# SDVX_Mini.net
KiCad netlist of a schematic drawn in Altium Designer
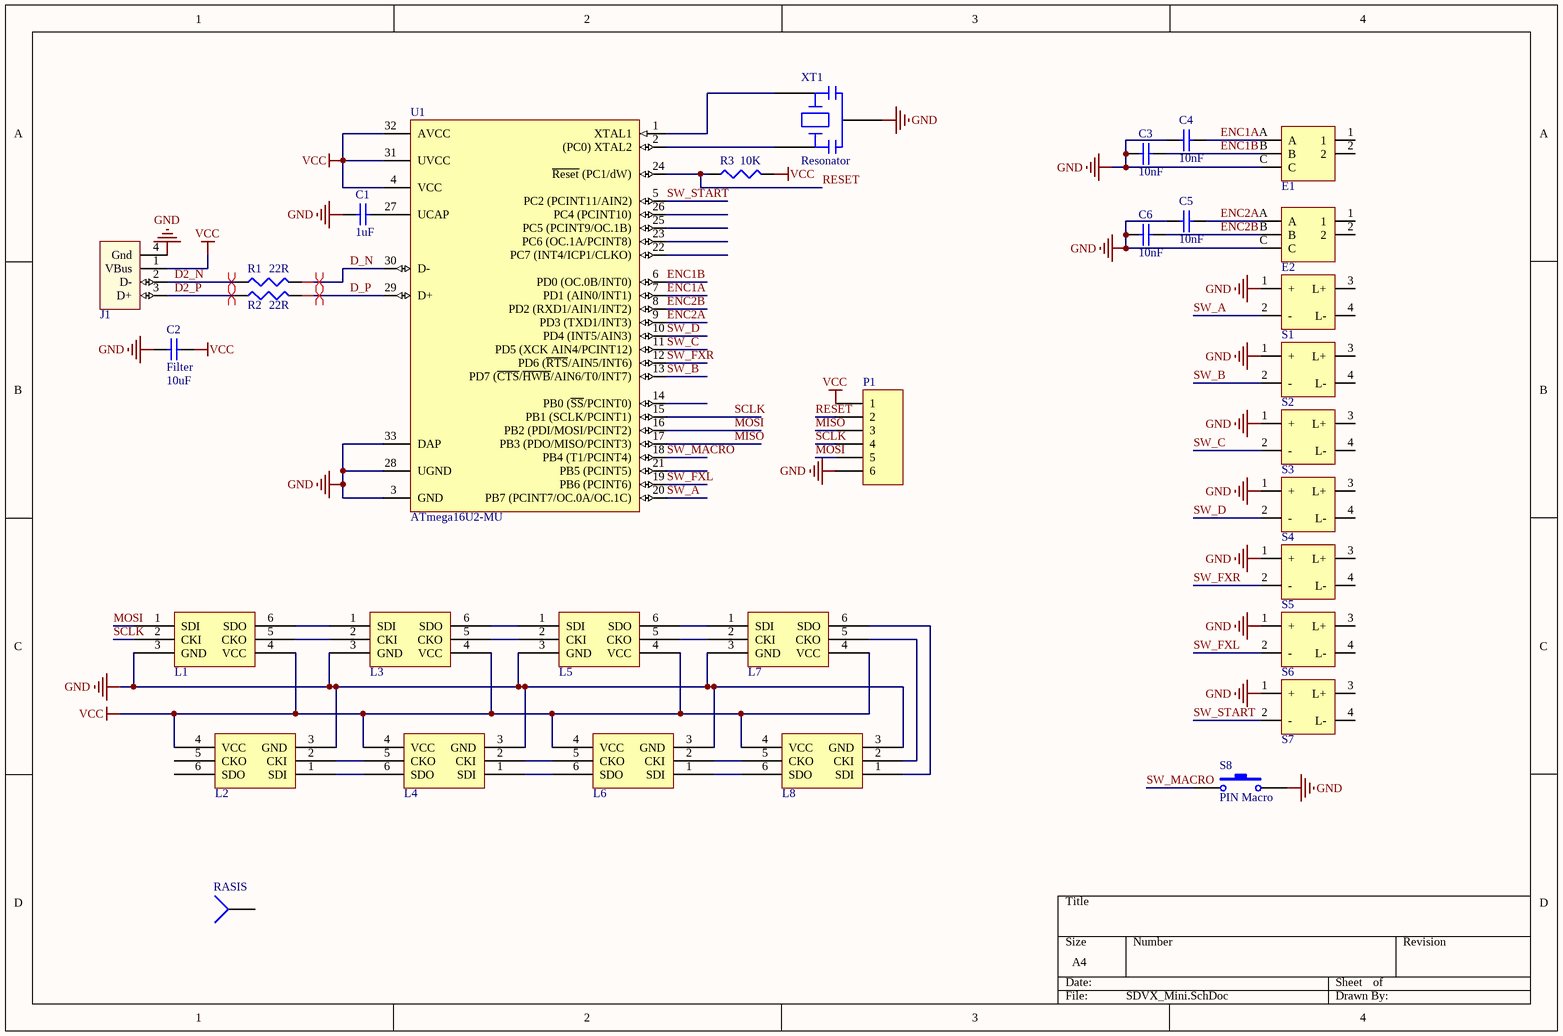
[diagram p0: SDVX_Mini.SchDoc]

(export (version "E")
  (design (tool "Eeschema 10.0.6"))
  (components
    (comp (ref "C1")
      (value "1uF")
      (footprint "1608[0603]")
      (description "Capacitor (Semiconductor SIM Model)")
      (fields (field (name "Comment") "Cap Semi") (field (name "PUBLISHER") "Altium Limited"))
      (libsource (lib "Miscellaneous Devices") (part "Cap Semi"))
    )
    (comp (ref "C2")
      (value "Filter")
      (footprint "1608[0603]")
      (description "Capacitor (Semiconductor SIM Model)")
      (fields (field (name "ALTIUM_VALUE") "10uF") (field (name "PUBLISHER") "Altium Limited"))
      (libsource (lib "Miscellaneous Devices") (part "Cap Semi"))
    )
    (comp (ref "C3")
      (value "10nF")
      (footprint "1608[0603]")
      (description "Capacitor (Semiconductor SIM Model)")
      (fields (field (name "Comment") "Cap Semi") (field (name "PUBLISHER") "Altium Limited"))
      (libsource (lib "Miscellaneous Devices") (part "Cap Semi"))
    )
    (comp (ref "C4")
      (value "10nF")
      (footprint "1608[0603]")
      (description "Capacitor (Semiconductor SIM Model)")
      (fields (field (name "Comment") "Cap Semi") (field (name "PUBLISHER") "Altium Limited"))
      (libsource (lib "Miscellaneous Devices") (part "Cap Semi"))
    )
    (comp (ref "C5")
      (value "10nF")
      (footprint "1608[0603]")
      (description "Capacitor (Semiconductor SIM Model)")
      (fields (field (name "Comment") "Cap Semi") (field (name "PUBLISHER") "Altium Limited"))
      (libsource (lib "Miscellaneous Devices") (part "Cap Semi"))
    )
    (comp (ref "C6")
      (value "10nF")
      (footprint "1608[0603]")
      (description "Capacitor (Semiconductor SIM Model)")
      (fields (field (name "Comment") "Cap Semi") (field (name "PUBLISHER") "Altium Limited"))
      (libsource (lib "Miscellaneous Devices") (part "Cap Semi"))
    )
    (comp (ref "E1")
      (value "ENCODER_SWITCH")
      (footprint "ENCODER_NOSWITCH_BOURNS_PEC16-4")
      (libsource (lib "MonParts") (part "ENCODER_SWITCH"))
    )
    (comp (ref "E2")
      (value "ENCODER_SWITCH")
      (footprint "ENCODER_NOSWITCH_BOURNS_PEC16-4")
      (libsource (lib "MonParts") (part "ENCODER_SWITCH"))
    )
    (comp (ref "J1")
      (value "USB Connector")
      (footprint "MICRO-USB-SEEED")
      (libsource (lib "MonParts") (part "USB Connector"))
    )
    (comp (ref "L1") (value "SK9822") (footprint "SK9822") (libsource (lib "") (part "SK9822_1")))
    (comp (ref "L2") (value "SK9822") (footprint "SK9822") (libsource (lib "MonParts") (part "SK9822")))
    (comp (ref "L3") (value "SK9822") (footprint "SK9822") (libsource (lib "") (part "SK9822_1")))
    (comp (ref "L4") (value "SK9822") (footprint "SK9822") (libsource (lib "MonParts") (part "SK9822")))
    (comp (ref "L5") (value "SK9822") (footprint "SK9822") (libsource (lib "") (part "SK9822_1")))
    (comp (ref "L6") (value "SK9822") (footprint "SK9822") (libsource (lib "MonParts") (part "SK9822")))
    (comp (ref "L7") (value "SK9822") (footprint "SK9822") (libsource (lib "") (part "SK9822_1")))
    (comp (ref "L8") (value "SK9822") (footprint "SK9822") (libsource (lib "MonParts") (part "SK9822")))
    (comp (ref "P1")
      (value "Header 6")
      (footprint "HDR1X6")
      (description "Header, 6-Pin")
      (fields (field (name "PUBLISHER") "Altium Limited"))
      (libsource (lib "Miscellaneous Connectors") (part "Header 6"))
    )
    (comp (ref "R1")
      (value "22R")
      (footprint "J1-0603")
      (description "Resistor")
      (fields (field (name "PUBLISHER") "Altium Limited"))
      (libsource (lib "Miscellaneous Devices") (part "Res3"))
    )
    (comp (ref "R2")
      (value "22R")
      (footprint "J1-0603")
      (description "Resistor")
      (fields (field (name "Comment") "Res3") (field (name "PUBLISHER") "Altium Limited"))
      (libsource (lib "Miscellaneous Devices") (part "Res3"))
    )
    (comp (ref "R3")
      (value "10K")
      (footprint "J1-0603")
      (description "Resistor")
      (fields (field (name "PUBLISHER") "Altium Limited"))
      (libsource (lib "Miscellaneous Devices") (part "Res3"))
    )
    (comp (ref "RASIS")
      (value "Imp")
      (footprint "RASIS_INVERT")
      (description "Socket")
      (fields (field (name "PUBLISHER") "Altium Limited"))
      (libsource (lib "Miscellaneous Connectors") (part "Socket"))
    )
    (comp (ref "S1")
      (value "Cherry MX")
      (footprint "CHERRYMX_NO_LED")
      (libsource (lib "MonParts") (part "Cherry MX"))
    )
    (comp (ref "S2")
      (value "Cherry MX")
      (footprint "CHERRYMX_NO_LED")
      (libsource (lib "MonParts") (part "Cherry MX"))
    )
    (comp (ref "S3")
      (value "Cherry MX")
      (footprint "CHERRYMX_NO_LED")
      (libsource (lib "MonParts") (part "Cherry MX"))
    )
    (comp (ref "S4")
      (value "Cherry MX")
      (footprint "CHERRYMX_NO_LED")
      (libsource (lib "MonParts") (part "Cherry MX"))
    )
    (comp (ref "S5")
      (value "Cherry MX")
      (footprint "CHERRYMX_NO_LED")
      (libsource (lib "MonParts") (part "Cherry MX"))
    )
    (comp (ref "S6")
      (value "Cherry MX")
      (footprint "CHERRYMX_NO_LED")
      (libsource (lib "MonParts") (part "Cherry MX"))
    )
    (comp (ref "S7")
      (value "Cherry MX")
      (footprint "CHERRYMX_NO_LED")
      (libsource (lib "MonParts") (part "Cherry MX"))
    )
    (comp (ref "S8")
      (value "PIN Macro")
      (footprint "SWITCH_KSC421J")
      (description "Switch")
      (fields (field (name "PUBLISHER") "Altium Limited"))
      (libsource (lib "Miscellaneous Devices") (part "SW-PB"))
    )
    (comp (ref "U1")
      (value "ATmega16U2-MU")
      (footprint "ATMEGA16U2-NOTHERMAL")
      (libsource (lib "Atmel Microcontroller megaAVR") (part "ATmega16U2-MU"))
    )
    (comp (ref "XT1")
      (value "Resonator")
      (footprint "RESONATOR_CSTCE_V")
      (libsource (lib "MonParts") (part "Resonator"))
    )
  )
  (nets
    (net (code "1") (name "/D2_N") (class "Default")
      (node (ref "J1") (pin "2") (pinfunction "D-_2") (pintype "bidirectional"))
      (node (ref "R1") (pin "1") (pinfunction "1_1") (pintype "passive"))
    )
    (net (code "2") (name "/D2_P") (class "Default")
      (node (ref "J1") (pin "3") (pinfunction "D+_3") (pintype "bidirectional"))
      (node (ref "R2") (pin "1") (pinfunction "1_1") (pintype "passive"))
    )
    (net (code "3") (name "/D_N") (class "Default")
      (node (ref "R1") (pin "2") (pinfunction "2_2") (pintype "passive"))
      (node (ref "U1") (pin "30") (pinfunction "D-_30") (pintype "bidirectional"))
    )
    (net (code "4") (name "/D_P") (class "Default")
      (node (ref "R2") (pin "2") (pinfunction "2_2") (pintype "passive"))
      (node (ref "U1") (pin "29") (pinfunction "D+_29") (pintype "bidirectional"))
    )
    (net (code "5") (name "/ENC1A") (class "Default")
      (node (ref "C4") (pin "1") (pinfunction "1_1") (pintype "passive"))
      (node (ref "E1") (pin "A") (pinfunction "A_A") (pintype "passive"))
      (node (ref "U1") (pin "7") (pinfunction "PD1_(AIN0/INT1)_7") (pintype "bidirectional"))
    )
    (net (code "6") (name "/ENC1B") (class "Default")
      (node (ref "C3") (pin "2") (pinfunction "2_2") (pintype "passive"))
      (node (ref "E1") (pin "B") (pinfunction "B_B") (pintype "passive"))
      (node (ref "U1") (pin "6") (pinfunction "PD0_(OC.0B/INT0)_6") (pintype "bidirectional"))
    )
    (net (code "7") (name "/ENC2A") (class "Default")
      (node (ref "C5") (pin "1") (pinfunction "1_1") (pintype "passive"))
      (node (ref "E2") (pin "A") (pinfunction "A_A") (pintype "passive"))
      (node (ref "U1") (pin "9") (pinfunction "PD3_(TXD1/INT3)_9") (pintype "bidirectional"))
    )
    (net (code "8") (name "/ENC2B") (class "Default")
      (node (ref "C6") (pin "2") (pinfunction "2_2") (pintype "passive"))
      (node (ref "E2") (pin "B") (pinfunction "B_B") (pintype "passive"))
      (node (ref "U1") (pin "8") (pinfunction "PD2_(RXD1/AIN1/INT2)_8") (pintype "bidirectional"))
    )
    (net (code "9") (name "/MISO") (class "Default")
      (node (ref "P1") (pin "3") (pinfunction "3_3") (pintype "passive"))
      (node (ref "U1") (pin "17") (pinfunction "PB3_(PDO/MISO/PCINT3)_17") (pintype "bidirectional"))
    )
    (net (code "10") (name "/MOSI") (class "Default")
      (node (ref "L1") (pin "1") (pinfunction "SDI_1") (pintype "passive"))
      (node (ref "P1") (pin "5") (pinfunction "5_5") (pintype "passive"))
      (node (ref "U1") (pin "16") (pinfunction "PB2_(PDI/MOSI/PCINT2)_16") (pintype "bidirectional"))
    )
    (net (code "11") (name "/RESET") (class "Default")
      (node (ref "P1") (pin "2") (pinfunction "2_2") (pintype "passive"))
      (node (ref "R3") (pin "1") (pinfunction "1_1") (pintype "passive"))
      (node (ref "U1") (pin "24") (pinfunction "~{Reset}_(PC1/dW)_24") (pintype "bidirectional"))
    )
    (net (code "12") (name "/SCLK") (class "Default")
      (node (ref "L1") (pin "2") (pinfunction "CKI_2") (pintype "passive"))
      (node (ref "P1") (pin "4") (pinfunction "4_4") (pintype "passive"))
      (node (ref "U1") (pin "15") (pinfunction "PB1_(SCLK/PCINT1)_15") (pintype "bidirectional"))
    )
    (net (code "13") (name "/SW_A") (class "Default")
      (node (ref "S1") (pin "2") (pinfunction "-_2") (pintype "passive"))
      (node (ref "U1") (pin "20") (pinfunction "PB7_(PCINT7/OC.0A/OC.1C)_20") (pintype "bidirectional"))
    )
    (net (code "14") (name "/SW_B") (class "Default")
      (node (ref "S2") (pin "2") (pinfunction "-_2") (pintype "passive"))
      (node (ref "U1") (pin "13") (pinfunction "PD7_(~{CTS}/~{HWB}/AIN6/T0/INT7)_13") (pintype "bidirectional"))
    )
    (net (code "15") (name "/SW_C") (class "Default")
      (node (ref "S3") (pin "2") (pinfunction "-_2") (pintype "passive"))
      (node (ref "U1") (pin "11") (pinfunction "PD5_(XCK_AIN4/PCINT12)_11") (pintype "bidirectional"))
    )
    (net (code "16") (name "/SW_D") (class "Default")
      (node (ref "S4") (pin "2") (pinfunction "-_2") (pintype "passive"))
      (node (ref "U1") (pin "10") (pinfunction "PD4_(INT5/AIN3)_10") (pintype "bidirectional"))
    )
    (net (code "17") (name "/SW_FXL") (class "Default")
      (node (ref "S6") (pin "2") (pinfunction "-_2") (pintype "passive"))
      (node (ref "U1") (pin "19") (pinfunction "PB6_(PCINT6)_19") (pintype "bidirectional"))
    )
    (net (code "18") (name "/SW_FXR") (class "Default")
      (node (ref "S5") (pin "2") (pinfunction "-_2") (pintype "passive"))
      (node (ref "U1") (pin "12") (pinfunction "PD6_(~{RTS}/AIN5/INT6)_12") (pintype "bidirectional"))
    )
    (net (code "19") (name "/SW_MACRO") (class "Default")
      (node (ref "S8") (pin "1") (pinfunction "1_1") (pintype "passive"))
      (node (ref "U1") (pin "18") (pinfunction "PB4_(T1/PCINT4)_18") (pintype "bidirectional"))
    )
    (net (code "20") (name "/SW_START") (class "Default")
      (node (ref "S7") (pin "2") (pinfunction "-_2") (pintype "passive"))
      (node (ref "U1") (pin "5") (pinfunction "PC2_(PCINT11/AIN2)_5") (pintype "bidirectional"))
    )
    (net (code "21") (name "GND") (class "Default")
      (node (ref "C1") (pin "2") (pinfunction "2_2") (pintype "passive"))
      (node (ref "C2") (pin "2") (pinfunction "2_2") (pintype "passive"))
      (node (ref "C3") (pin "1") (pinfunction "1_1") (pintype "passive"))
      (node (ref "C4") (pin "2") (pinfunction "2_2") (pintype "passive"))
      (node (ref "C5") (pin "2") (pinfunction "2_2") (pintype "passive"))
      (node (ref "C6") (pin "1") (pinfunction "1_1") (pintype "passive"))
      (node (ref "E1") (pin "C") (pinfunction "C_C") (pintype "passive"))
      (node (ref "E2") (pin "C") (pinfunction "C_C") (pintype "passive"))
      (node (ref "J1") (pin "4") (pinfunction "Gnd_4") (pintype "power_in"))
      (node (ref "L1") (pin "3") (pinfunction "GND_3") (pintype "passive"))
      (node (ref "L2") (pin "3") (pinfunction "GND_3") (pintype "passive"))
      (node (ref "L3") (pin "3") (pinfunction "GND_3") (pintype "passive"))
      (node (ref "L4") (pin "3") (pinfunction "GND_3") (pintype "passive"))
      (node (ref "L5") (pin "3") (pinfunction "GND_3") (pintype "passive"))
      (node (ref "L6") (pin "3") (pinfunction "GND_3") (pintype "passive"))
      (node (ref "L7") (pin "3") (pinfunction "GND_3") (pintype "passive"))
      (node (ref "L8") (pin "3") (pinfunction "GND_3") (pintype "passive"))
      (node (ref "P1") (pin "6") (pinfunction "6_6") (pintype "passive"))
      (node (ref "S1") (pin "1") (pinfunction "+_1") (pintype "passive"))
      (node (ref "S2") (pin "1") (pinfunction "+_1") (pintype "passive"))
      (node (ref "S3") (pin "1") (pinfunction "+_1") (pintype "passive"))
      (node (ref "S4") (pin "1") (pinfunction "+_1") (pintype "passive"))
      (node (ref "S5") (pin "1") (pinfunction "+_1") (pintype "passive"))
      (node (ref "S6") (pin "1") (pinfunction "+_1") (pintype "passive"))
      (node (ref "S7") (pin "1") (pinfunction "+_1") (pintype "passive"))
      (node (ref "S8") (pin "2") (pinfunction "2_2") (pintype "passive"))
      (node (ref "U1") (pin "28") (pinfunction "UGND_28") (pintype "power_in"))
      (node (ref "U1") (pin "3") (pinfunction "GND_3") (pintype "power_in"))
      (node (ref "U1") (pin "33") (pinfunction "DAP_33") (pintype "power_in"))
      (node (ref "XT1") (pin "2") (pinfunction "2_2") (pintype "passive"))
    )
    (net (code "22") (name "Net-(L1-CKO)") (class "Default")
      (node (ref "L1") (pin "5") (pinfunction "CKO_5") (pintype "passive"))
      (node (ref "L3") (pin "2") (pinfunction "CKI_2") (pintype "passive"))
    )
    (net (code "23") (name "Net-(L1-SDO)") (class "Default")
      (node (ref "L1") (pin "6") (pinfunction "SDO_6") (pintype "passive"))
      (node (ref "L3") (pin "1") (pinfunction "SDI_1") (pintype "passive"))
    )
    (net (code "24") (name "Net-(L2-CKI)") (class "Default")
      (node (ref "L2") (pin "2") (pinfunction "CKI_2") (pintype "passive"))
      (node (ref "L4") (pin "5") (pinfunction "CKO_5") (pintype "passive"))
    )
    (net (code "25") (name "Net-(L2-SDI)") (class "Default")
      (node (ref "L2") (pin "1") (pinfunction "SDI_1") (pintype "passive"))
      (node (ref "L4") (pin "6") (pinfunction "SDO_6") (pintype "passive"))
    )
    (net (code "26") (name "Net-(L3-CKO)") (class "Default")
      (node (ref "L3") (pin "5") (pinfunction "CKO_5") (pintype "passive"))
      (node (ref "L5") (pin "2") (pinfunction "CKI_2") (pintype "passive"))
    )
    (net (code "27") (name "Net-(L3-SDO)") (class "Default")
      (node (ref "L3") (pin "6") (pinfunction "SDO_6") (pintype "passive"))
      (node (ref "L5") (pin "1") (pinfunction "SDI_1") (pintype "passive"))
    )
    (net (code "28") (name "Net-(L4-CKI)") (class "Default")
      (node (ref "L4") (pin "2") (pinfunction "CKI_2") (pintype "passive"))
      (node (ref "L6") (pin "5") (pinfunction "CKO_5") (pintype "passive"))
    )
    (net (code "29") (name "Net-(L4-SDI)") (class "Default")
      (node (ref "L4") (pin "1") (pinfunction "SDI_1") (pintype "passive"))
      (node (ref "L6") (pin "6") (pinfunction "SDO_6") (pintype "passive"))
    )
    (net (code "30") (name "Net-(L5-CKO)") (class "Default")
      (node (ref "L5") (pin "5") (pinfunction "CKO_5") (pintype "passive"))
      (node (ref "L7") (pin "2") (pinfunction "CKI_2") (pintype "passive"))
    )
    (net (code "31") (name "Net-(L5-SDO)") (class "Default")
      (node (ref "L5") (pin "6") (pinfunction "SDO_6") (pintype "passive"))
      (node (ref "L7") (pin "1") (pinfunction "SDI_1") (pintype "passive"))
    )
    (net (code "32") (name "Net-(L6-CKI)") (class "Default")
      (node (ref "L6") (pin "2") (pinfunction "CKI_2") (pintype "passive"))
      (node (ref "L8") (pin "5") (pinfunction "CKO_5") (pintype "passive"))
    )
    (net (code "33") (name "Net-(L6-SDI)") (class "Default")
      (node (ref "L6") (pin "1") (pinfunction "SDI_1") (pintype "passive"))
      (node (ref "L8") (pin "6") (pinfunction "SDO_6") (pintype "passive"))
    )
    (net (code "34") (name "Net-(L7-CKO)") (class "Default")
      (node (ref "L7") (pin "5") (pinfunction "CKO_5") (pintype "passive"))
      (node (ref "L8") (pin "2") (pinfunction "CKI_2") (pintype "passive"))
    )
    (net (code "35") (name "Net-(L7-SDO)") (class "Default")
      (node (ref "L7") (pin "6") (pinfunction "SDO_6") (pintype "passive"))
      (node (ref "L8") (pin "1") (pinfunction "SDI_1") (pintype "passive"))
    )
    (net (code "36") (name "Net-(U1-(PC0)_XTAL2)") (class "Default")
      (node (ref "U1") (pin "2") (pinfunction "(PC0)_XTAL2_2") (pintype "bidirectional"))
      (node (ref "XT1") (pin "1") (pinfunction "1_1") (pintype "passive"))
    )
    (net (code "37") (name "Net-(U1-UCAP)") (class "Default")
      (node (ref "C1") (pin "1") (pinfunction "1_1") (pintype "passive"))
      (node (ref "U1") (pin "27") (pinfunction "UCAP_27") (pintype "power_in"))
    )
    (net (code "38") (name "Net-(U1-XTAL1)") (class "Default")
      (node (ref "U1") (pin "1") (pinfunction "XTAL1_1") (pintype "input"))
      (node (ref "XT1") (pin "3") (pinfunction "1_3") (pintype "passive"))
    )
    (net (code "39") (name "VCC") (class "Default")
      (node (ref "C2") (pin "1") (pinfunction "1_1") (pintype "passive"))
      (node (ref "J1") (pin "1") (pinfunction "VBus_1") (pintype "power_in"))
      (node (ref "L1") (pin "4") (pinfunction "VCC_4") (pintype "passive"))
      (node (ref "L2") (pin "4") (pinfunction "VCC_4") (pintype "passive"))
      (node (ref "L3") (pin "4") (pinfunction "VCC_4") (pintype "passive"))
      (node (ref "L4") (pin "4") (pinfunction "VCC_4") (pintype "passive"))
      (node (ref "L5") (pin "4") (pinfunction "VCC_4") (pintype "passive"))
      (node (ref "L6") (pin "4") (pinfunction "VCC_4") (pintype "passive"))
      (node (ref "L7") (pin "4") (pinfunction "VCC_4") (pintype "passive"))
      (node (ref "L8") (pin "4") (pinfunction "VCC_4") (pintype "passive"))
      (node (ref "P1") (pin "1") (pinfunction "1_1") (pintype "passive"))
      (node (ref "R3") (pin "2") (pinfunction "2_2") (pintype "passive"))
      (node (ref "U1") (pin "31") (pinfunction "UVCC_31") (pintype "power_in"))
      (node (ref "U1") (pin "32") (pinfunction "AVCC_32") (pintype "power_in"))
      (node (ref "U1") (pin "4") (pinfunction "VCC_4") (pintype "power_in"))
    )
    (net (code "40") (name "unconnected-(E1-Pad1)") (class "Default")
      (node (ref "E1") (pin "1") (pinfunction "1_1") (pintype "passive"))
    )
    (net (code "41") (name "unconnected-(E1-Pad2)") (class "Default")
      (node (ref "E1") (pin "2") (pinfunction "2_2") (pintype "passive"))
    )
    (net (code "42") (name "unconnected-(E2-Pad1)") (class "Default")
      (node (ref "E2") (pin "1") (pinfunction "1_1") (pintype "passive"))
    )
    (net (code "43") (name "unconnected-(E2-Pad2)") (class "Default")
      (node (ref "E2") (pin "2") (pinfunction "2_2") (pintype "passive"))
    )
    (net (code "44") (name "unconnected-(L2-CKO-Pad5)") (class "Default")
      (node (ref "L2") (pin "5") (pinfunction "CKO_5") (pintype "passive"))
    )
    (net (code "45") (name "unconnected-(L2-SDO-Pad6)") (class "Default")
      (node (ref "L2") (pin "6") (pinfunction "SDO_6") (pintype "passive"))
    )
    (net (code "46") (name "unconnected-(RASIS-Pad1)") (class "Default")
      (node (ref "RASIS") (pin "1") (pinfunction "1_1") (pintype "passive"))
    )
    (net (code "47") (name "unconnected-(S1-L+-Pad3)") (class "Default")
      (node (ref "S1") (pin "3") (pinfunction "L+_3") (pintype "passive"))
    )
    (net (code "48") (name "unconnected-(S1-L--Pad4)") (class "Default")
      (node (ref "S1") (pin "4") (pinfunction "L-_4") (pintype "passive"))
    )
    (net (code "49") (name "unconnected-(S2-L+-Pad3)") (class "Default")
      (node (ref "S2") (pin "3") (pinfunction "L+_3") (pintype "passive"))
    )
    (net (code "50") (name "unconnected-(S2-L--Pad4)") (class "Default")
      (node (ref "S2") (pin "4") (pinfunction "L-_4") (pintype "passive"))
    )
    (net (code "51") (name "unconnected-(S3-L+-Pad3)") (class "Default")
      (node (ref "S3") (pin "3") (pinfunction "L+_3") (pintype "passive"))
    )
    (net (code "52") (name "unconnected-(S3-L--Pad4)") (class "Default")
      (node (ref "S3") (pin "4") (pinfunction "L-_4") (pintype "passive"))
    )
    (net (code "53") (name "unconnected-(S4-L+-Pad3)") (class "Default")
      (node (ref "S4") (pin "3") (pinfunction "L+_3") (pintype "passive"))
    )
    (net (code "54") (name "unconnected-(S4-L--Pad4)") (class "Default")
      (node (ref "S4") (pin "4") (pinfunction "L-_4") (pintype "passive"))
    )
    (net (code "55") (name "unconnected-(S5-L+-Pad3)") (class "Default")
      (node (ref "S5") (pin "3") (pinfunction "L+_3") (pintype "passive"))
    )
    (net (code "56") (name "unconnected-(S5-L--Pad4)") (class "Default")
      (node (ref "S5") (pin "4") (pinfunction "L-_4") (pintype "passive"))
    )
    (net (code "57") (name "unconnected-(S6-L+-Pad3)") (class "Default")
      (node (ref "S6") (pin "3") (pinfunction "L+_3") (pintype "passive"))
    )
    (net (code "58") (name "unconnected-(S6-L--Pad4)") (class "Default")
      (node (ref "S6") (pin "4") (pinfunction "L-_4") (pintype "passive"))
    )
    (net (code "59") (name "unconnected-(S7-L+-Pad3)") (class "Default")
      (node (ref "S7") (pin "3") (pinfunction "L+_3") (pintype "passive"))
    )
    (net (code "60") (name "unconnected-(S7-L--Pad4)") (class "Default")
      (node (ref "S7") (pin "4") (pinfunction "L-_4") (pintype "passive"))
    )
    (net (code "61") (name "unconnected-(U1-PB0_(~{SS}{slash}PCINT0)-Pad14)") (class "Default")
      (node (ref "U1") (pin "14") (pinfunction "PB0_(~{SS}/PCINT0)_14") (pintype "bidirectional"))
    )
    (net (code "62") (name "unconnected-(U1-PB5_(PCINT5)-Pad21)") (class "Default")
      (node (ref "U1") (pin "21") (pinfunction "PB5_(PCINT5)_21") (pintype "bidirectional"))
    )
    (net (code "63") (name "unconnected-(U1-PC4_(PCINT10)-Pad26)") (class "Default")
      (node (ref "U1") (pin "26") (pinfunction "PC4_(PCINT10)_26") (pintype "bidirectional"))
    )
    (net (code "64") (name "unconnected-(U1-PC5_(PCINT9{slash}OC.1B)-Pad25)") (class "Default")
      (node (ref "U1") (pin "25") (pinfunction "PC5_(PCINT9/OC.1B)_25") (pintype "bidirectional"))
    )
    (net (code "65") (name "unconnected-(U1-PC6_(OC.1A{slash}PCINT8)-Pad23)") (class "Default")
      (node (ref "U1") (pin "23") (pinfunction "PC6_(OC.1A/PCINT8)_23") (pintype "bidirectional"))
    )
    (net (code "66") (name "unconnected-(U1-PC7_(INT4{slash}ICP1{slash}CLKO)-Pad22)") (class "Default")
      (node (ref "U1") (pin "22") (pinfunction "PC7_(INT4/ICP1/CLKO)_22") (pintype "bidirectional"))
    )
  )
)
